# Sheet2.net
KiCad netlist of a schematic drawn in Altium Designer
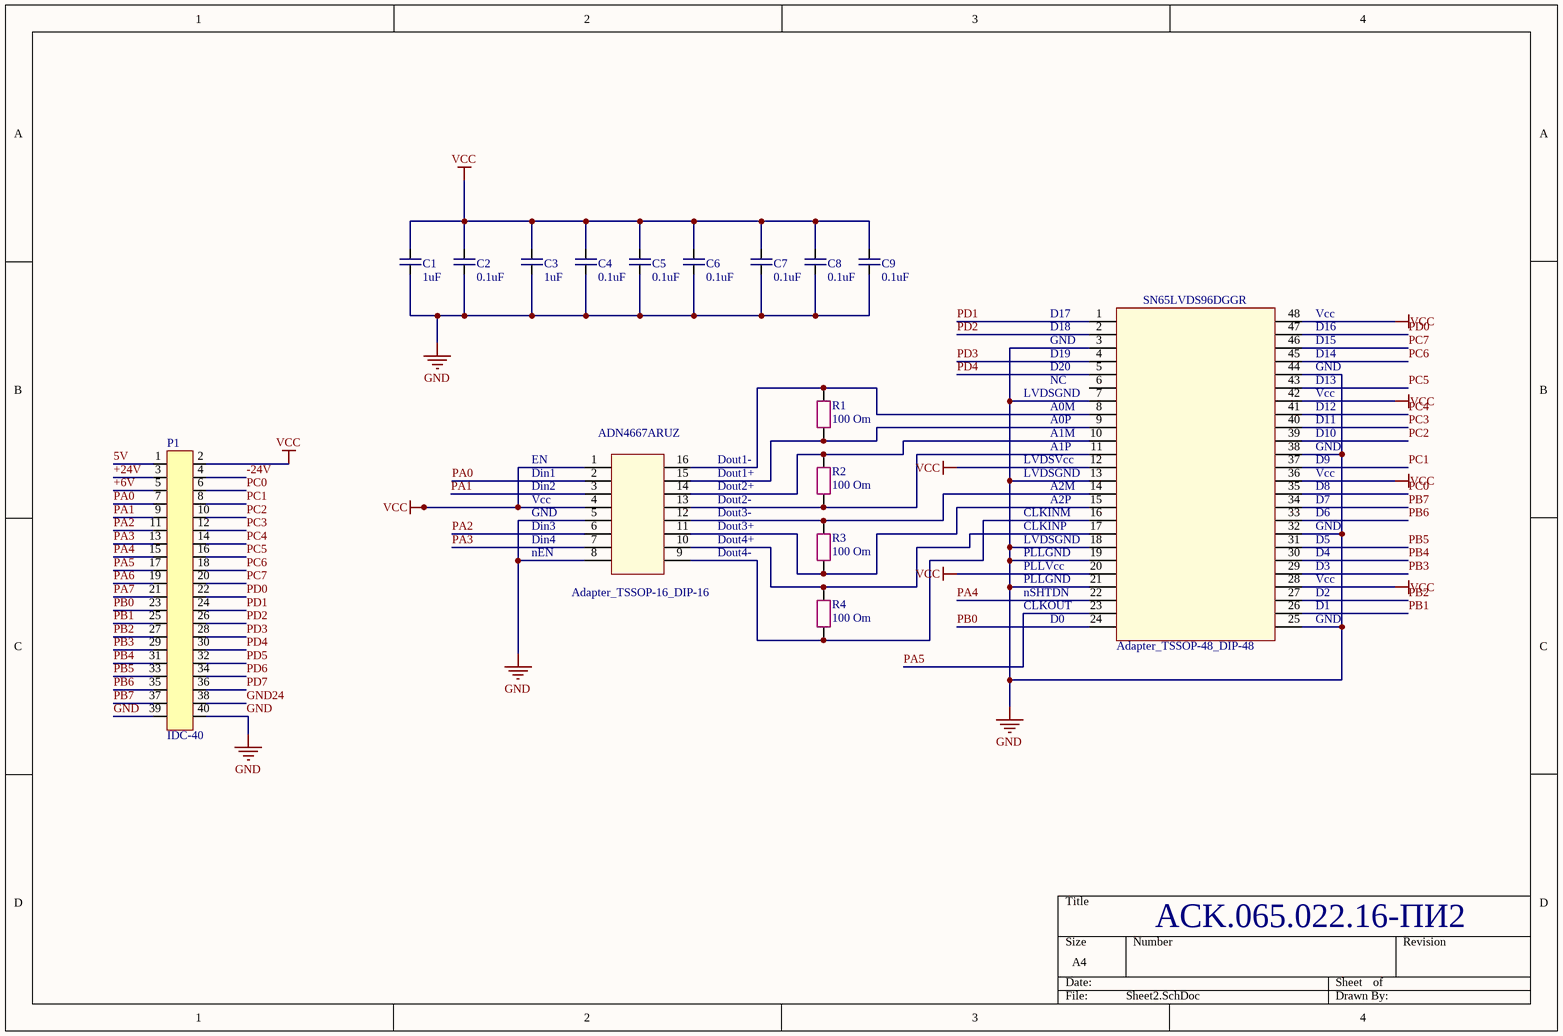
[diagram p0: Sheet2.SchDoc]

(export (version "E")
  (design (tool "Eeschema 10.0.6"))
  (components
    (comp (ref "ADN4667ARUZ")
      (value "Adapter_TSSOP-16_DIP-16")
      (footprint "Adapter_TSSOP-16_DIP-16")
      (libsource (lib "RCU") (part "Adapter_TSSOP-16_DIP-16"))
    )
    (comp (ref "C1") (value "1uF") (footprint "RCU:C_0805") (libsource (lib "RCU") (part "capacitor 0805")))
    (comp (ref "C2") (value "0.1uF") (footprint "RCU:C_0805") (libsource (lib "RCU") (part "capacitor 0805")))
    (comp (ref "C3") (value "1uF") (footprint "RCU:C_0805") (libsource (lib "RCU") (part "capacitor 0805")))
    (comp (ref "C4") (value "0.1uF") (footprint "RCU:C_0805") (libsource (lib "RCU") (part "capacitor 0805")))
    (comp (ref "C5") (value "0.1uF") (footprint "RCU:C_0805") (libsource (lib "RCU") (part "capacitor 0805")))
    (comp (ref "C6") (value "0.1uF") (footprint "RCU:C_0805") (libsource (lib "RCU") (part "capacitor 0805")))
    (comp (ref "C7") (value "0.1uF") (footprint "RCU:C_0805") (libsource (lib "RCU") (part "capacitor 0805")))
    (comp (ref "C8") (value "0.1uF") (footprint "RCU:C_0805") (libsource (lib "RCU") (part "capacitor 0805")))
    (comp (ref "C9") (value "0.1uF") (footprint "RCU:C_0805") (libsource (lib "RCU") (part "capacitor 0805")))
    (comp (ref "P1")
      (value "IDC-40")
      (footprint "IDC-40")
      (description "разъем 2529")
      (libsource (lib "RCU") (part "IDC-40"))
    )
    (comp (ref "R1") (value "100 Om") (footprint "RCU:R_0805") (libsource (lib "RCU") (part "resistor 0805")))
    (comp (ref "R2") (value "100 Om") (footprint "RCU:R_0805") (libsource (lib "RCU") (part "resistor 0805")))
    (comp (ref "R3") (value "100 Om") (footprint "RCU:R_0805") (libsource (lib "RCU") (part "resistor 0805")))
    (comp (ref "R4") (value "100 Om") (footprint "RCU:R_0805") (libsource (lib "RCU") (part "resistor 0805")))
    (comp (ref "SN65LVDS96DGGR")
      (value "Adapter_TSSOP-48_DIP-48")
      (footprint "Adapter_TSSOP-48_DIP-48")
      (libsource (lib "RCU") (part "Adapter_TSSOP-48_DIP-48"))
    )
  )
  (nets
    (net (code "1") (name "/+6V") (class "Default")
      (node (ref "P1") (pin "5") (pinfunction "5_5") (pintype "passive"))
    )
    (net (code "2") (name "/+24V") (class "Default")
      (node (ref "P1") (pin "3") (pinfunction "3_3") (pintype "passive"))
    )
    (net (code "3") (name "/-24V") (class "Default")
      (node (ref "P1") (pin "4") (pinfunction "4_4") (pintype "passive"))
    )
    (net (code "4") (name "/5V") (class "Default")
      (node (ref "P1") (pin "1") (pinfunction "0_1") (pintype "passive"))
    )
    (net (code "5") (name "/GND24") (class "Default")
      (node (ref "P1") (pin "38") (pinfunction "38_38") (pintype "passive"))
    )
    (net (code "6") (name "/PA0") (class "Default")
      (node (ref "ADN4667ARUZ") (pin "2") (pinfunction "2_2") (pintype "passive"))
      (node (ref "P1") (pin "7") (pinfunction "7_7") (pintype "passive"))
    )
    (net (code "7") (name "/PA1") (class "Default")
      (node (ref "ADN4667ARUZ") (pin "3") (pinfunction "3_3") (pintype "passive"))
      (node (ref "P1") (pin "9") (pinfunction "9_9") (pintype "passive"))
    )
    (net (code "8") (name "/PA2") (class "Default")
      (node (ref "ADN4667ARUZ") (pin "6") (pinfunction "6_6") (pintype "passive"))
      (node (ref "P1") (pin "11") (pinfunction "11_11") (pintype "passive"))
    )
    (net (code "9") (name "/PA3") (class "Default")
      (node (ref "ADN4667ARUZ") (pin "7") (pinfunction "7_7") (pintype "passive"))
      (node (ref "P1") (pin "13") (pinfunction "13_13") (pintype "passive"))
    )
    (net (code "10") (name "/PA4") (class "Default")
      (node (ref "P1") (pin "15") (pinfunction "15_15") (pintype "passive"))
      (node (ref "SN65LVDS96DGGR") (pin "22") (pinfunction "22_22") (pintype "passive"))
    )
    (net (code "11") (name "/PA5") (class "Default")
      (node (ref "P1") (pin "17") (pinfunction "17_17") (pintype "passive"))
      (node (ref "SN65LVDS96DGGR") (pin "23") (pinfunction "23_23") (pintype "passive"))
    )
    (net (code "12") (name "/PA6") (class "Default")
      (node (ref "P1") (pin "19") (pinfunction "19_19") (pintype "passive"))
    )
    (net (code "13") (name "/PA7") (class "Default")
      (node (ref "P1") (pin "21") (pinfunction "21_21") (pintype "passive"))
    )
    (net (code "14") (name "/PB0") (class "Default")
      (node (ref "P1") (pin "23") (pinfunction "23_23") (pintype "passive"))
      (node (ref "SN65LVDS96DGGR") (pin "24") (pinfunction "24_24") (pintype "passive"))
    )
    (net (code "15") (name "/PB1") (class "Default")
      (node (ref "P1") (pin "25") (pinfunction "25_25") (pintype "passive"))
      (node (ref "SN65LVDS96DGGR") (pin "26") (pinfunction "26_26") (pintype "passive"))
    )
    (net (code "16") (name "/PB2") (class "Default")
      (node (ref "P1") (pin "27") (pinfunction "27_27") (pintype "passive"))
      (node (ref "SN65LVDS96DGGR") (pin "27") (pinfunction "27_27") (pintype "passive"))
    )
    (net (code "17") (name "/PB3") (class "Default")
      (node (ref "P1") (pin "29") (pinfunction "29_29") (pintype "passive"))
      (node (ref "SN65LVDS96DGGR") (pin "29") (pinfunction "29_29") (pintype "passive"))
    )
    (net (code "18") (name "/PB4") (class "Default")
      (node (ref "P1") (pin "31") (pinfunction "31_31") (pintype "passive"))
      (node (ref "SN65LVDS96DGGR") (pin "30") (pinfunction "30_30") (pintype "passive"))
    )
    (net (code "19") (name "/PB5") (class "Default")
      (node (ref "P1") (pin "33") (pinfunction "33_33") (pintype "passive"))
      (node (ref "SN65LVDS96DGGR") (pin "31") (pinfunction "31_31") (pintype "passive"))
    )
    (net (code "20") (name "/PB6") (class "Default")
      (node (ref "P1") (pin "35") (pinfunction "35_35") (pintype "passive"))
      (node (ref "SN65LVDS96DGGR") (pin "33") (pinfunction "33_33") (pintype "passive"))
    )
    (net (code "21") (name "/PB7") (class "Default")
      (node (ref "P1") (pin "37") (pinfunction "37_37") (pintype "passive"))
      (node (ref "SN65LVDS96DGGR") (pin "34") (pinfunction "34_34") (pintype "passive"))
    )
    (net (code "22") (name "/PC0") (class "Default")
      (node (ref "P1") (pin "6") (pinfunction "6_6") (pintype "passive"))
      (node (ref "SN65LVDS96DGGR") (pin "35") (pinfunction "35_35") (pintype "passive"))
    )
    (net (code "23") (name "/PC1") (class "Default")
      (node (ref "P1") (pin "8") (pinfunction "8_8") (pintype "passive"))
      (node (ref "SN65LVDS96DGGR") (pin "37") (pinfunction "37_37") (pintype "passive"))
    )
    (net (code "24") (name "/PC2") (class "Default")
      (node (ref "P1") (pin "10") (pinfunction "10_10") (pintype "passive"))
      (node (ref "SN65LVDS96DGGR") (pin "39") (pinfunction "39_39") (pintype "passive"))
    )
    (net (code "25") (name "/PC3") (class "Default")
      (node (ref "P1") (pin "12") (pinfunction "12_12") (pintype "passive"))
      (node (ref "SN65LVDS96DGGR") (pin "40") (pinfunction "40_40") (pintype "passive"))
    )
    (net (code "26") (name "/PC4") (class "Default")
      (node (ref "P1") (pin "14") (pinfunction "14_14") (pintype "passive"))
      (node (ref "SN65LVDS96DGGR") (pin "41") (pinfunction "41_41") (pintype "passive"))
    )
    (net (code "27") (name "/PC5") (class "Default")
      (node (ref "P1") (pin "16") (pinfunction "16_16") (pintype "passive"))
      (node (ref "SN65LVDS96DGGR") (pin "43") (pinfunction "43_43") (pintype "passive"))
    )
    (net (code "28") (name "/PC6") (class "Default")
      (node (ref "P1") (pin "18") (pinfunction "18_18") (pintype "passive"))
      (node (ref "SN65LVDS96DGGR") (pin "45") (pinfunction "45_45") (pintype "passive"))
    )
    (net (code "29") (name "/PC7") (class "Default")
      (node (ref "P1") (pin "20") (pinfunction "20_20") (pintype "passive"))
      (node (ref "SN65LVDS96DGGR") (pin "46") (pinfunction "46_46") (pintype "passive"))
    )
    (net (code "30") (name "/PD0") (class "Default")
      (node (ref "P1") (pin "22") (pinfunction "22_22") (pintype "passive"))
      (node (ref "SN65LVDS96DGGR") (pin "47") (pinfunction "47_47") (pintype "passive"))
    )
    (net (code "31") (name "/PD1") (class "Default")
      (node (ref "P1") (pin "24") (pinfunction "24_24") (pintype "passive"))
      (node (ref "SN65LVDS96DGGR") (pin "1") (pinfunction "1_1") (pintype "passive"))
    )
    (net (code "32") (name "/PD2") (class "Default")
      (node (ref "P1") (pin "26") (pinfunction "26_26") (pintype "passive"))
      (node (ref "SN65LVDS96DGGR") (pin "2") (pinfunction "2_2") (pintype "passive"))
    )
    (net (code "33") (name "/PD3") (class "Default")
      (node (ref "P1") (pin "28") (pinfunction "28_28") (pintype "passive"))
      (node (ref "SN65LVDS96DGGR") (pin "4") (pinfunction "4_4") (pintype "passive"))
    )
    (net (code "34") (name "/PD4") (class "Default")
      (node (ref "P1") (pin "30") (pinfunction "30_30") (pintype "passive"))
      (node (ref "SN65LVDS96DGGR") (pin "5") (pinfunction "5_5") (pintype "passive"))
    )
    (net (code "35") (name "/PD5") (class "Default")
      (node (ref "P1") (pin "32") (pinfunction "32_32") (pintype "passive"))
    )
    (net (code "36") (name "/PD6") (class "Default")
      (node (ref "P1") (pin "34") (pinfunction "34_34") (pintype "passive"))
    )
    (net (code "37") (name "/PD7") (class "Default")
      (node (ref "P1") (pin "36") (pinfunction "36_36") (pintype "passive"))
    )
    (net (code "38") (name "GND") (class "Default")
      (node (ref "ADN4667ARUZ") (pin "5") (pinfunction "5_5") (pintype "passive"))
      (node (ref "ADN4667ARUZ") (pin "8") (pinfunction "8_8") (pintype "passive"))
      (node (ref "C1") (pin "2") (pinfunction "2_2") (pintype "passive"))
      (node (ref "C2") (pin "2") (pinfunction "2_2") (pintype "passive"))
      (node (ref "C3") (pin "2") (pinfunction "2_2") (pintype "passive"))
      (node (ref "C4") (pin "2") (pinfunction "2_2") (pintype "passive"))
      (node (ref "C5") (pin "2") (pinfunction "2_2") (pintype "passive"))
      (node (ref "C6") (pin "2") (pinfunction "2_2") (pintype "passive"))
      (node (ref "C7") (pin "2") (pinfunction "2_2") (pintype "passive"))
      (node (ref "C8") (pin "2") (pinfunction "2_2") (pintype "passive"))
      (node (ref "C9") (pin "2") (pinfunction "2_2") (pintype "passive"))
      (node (ref "P1") (pin "39") (pinfunction "39_39") (pintype "passive"))
      (node (ref "P1") (pin "40") (pinfunction "40_40") (pintype "passive"))
      (node (ref "SN65LVDS96DGGR") (pin "13") (pinfunction "13_13") (pintype "passive"))
      (node (ref "SN65LVDS96DGGR") (pin "18") (pinfunction "18_18") (pintype "passive"))
      (node (ref "SN65LVDS96DGGR") (pin "19") (pinfunction "19_19") (pintype "passive"))
      (node (ref "SN65LVDS96DGGR") (pin "21") (pinfunction "21_21") (pintype "passive"))
      (node (ref "SN65LVDS96DGGR") (pin "25") (pinfunction "25_25") (pintype "passive"))
      (node (ref "SN65LVDS96DGGR") (pin "3") (pinfunction "3_3") (pintype "passive"))
      (node (ref "SN65LVDS96DGGR") (pin "32") (pinfunction "32_32") (pintype "passive"))
      (node (ref "SN65LVDS96DGGR") (pin "38") (pinfunction "38_38") (pintype "passive"))
      (node (ref "SN65LVDS96DGGR") (pin "44") (pinfunction "44_44") (pintype "passive"))
      (node (ref "SN65LVDS96DGGR") (pin "7") (pinfunction "7_7") (pintype "passive"))
    )
    (net (code "39") (name "Net-(ADN4667ARUZ-Pad9)") (class "Default")
      (node (ref "ADN4667ARUZ") (pin "9") (pinfunction "9_9") (pintype "passive"))
      (node (ref "R4") (pin "1") (pinfunction "1_1") (pintype "passive"))
      (node (ref "SN65LVDS96DGGR") (pin "16") (pinfunction "16_16") (pintype "passive"))
    )
    (net (code "40") (name "Net-(ADN4667ARUZ-Pad10)") (class "Default")
      (node (ref "ADN4667ARUZ") (pin "10") (pinfunction "10_10") (pintype "passive"))
      (node (ref "R4") (pin "2") (pinfunction "2_2") (pintype "passive"))
      (node (ref "SN65LVDS96DGGR") (pin "17") (pinfunction "17_17") (pintype "passive"))
    )
    (net (code "41") (name "Net-(ADN4667ARUZ-Pad11)") (class "Default")
      (node (ref "ADN4667ARUZ") (pin "11") (pinfunction "11_11") (pintype "passive"))
      (node (ref "R3") (pin "1") (pinfunction "1_1") (pintype "passive"))
      (node (ref "SN65LVDS96DGGR") (pin "15") (pinfunction "15_15") (pintype "passive"))
    )
    (net (code "42") (name "Net-(ADN4667ARUZ-Pad12)") (class "Default")
      (node (ref "ADN4667ARUZ") (pin "12") (pinfunction "12_12") (pintype "passive"))
      (node (ref "R3") (pin "2") (pinfunction "2_2") (pintype "passive"))
      (node (ref "SN65LVDS96DGGR") (pin "14") (pinfunction "14_14") (pintype "passive"))
    )
    (net (code "43") (name "Net-(ADN4667ARUZ-Pad13)") (class "Default")
      (node (ref "ADN4667ARUZ") (pin "13") (pinfunction "13_13") (pintype "passive"))
      (node (ref "R2") (pin "1") (pinfunction "1_1") (pintype "passive"))
      (node (ref "SN65LVDS96DGGR") (pin "11") (pinfunction "11_11") (pintype "passive"))
    )
    (net (code "44") (name "Net-(ADN4667ARUZ-Pad14)") (class "Default")
      (node (ref "ADN4667ARUZ") (pin "14") (pinfunction "14_14") (pintype "passive"))
      (node (ref "R2") (pin "2") (pinfunction "2_2") (pintype "passive"))
      (node (ref "SN65LVDS96DGGR") (pin "10") (pinfunction "10_10") (pintype "passive"))
    )
    (net (code "45") (name "Net-(ADN4667ARUZ-Pad15)") (class "Default")
      (node (ref "ADN4667ARUZ") (pin "15") (pinfunction "15_15") (pintype "passive"))
      (node (ref "R1") (pin "1") (pinfunction "1_1") (pintype "passive"))
      (node (ref "SN65LVDS96DGGR") (pin "9") (pinfunction "9_9") (pintype "passive"))
    )
    (net (code "46") (name "Net-(ADN4667ARUZ-Pad16)") (class "Default")
      (node (ref "ADN4667ARUZ") (pin "16") (pinfunction "16_16") (pintype "passive"))
      (node (ref "R1") (pin "2") (pinfunction "2_2") (pintype "passive"))
      (node (ref "SN65LVDS96DGGR") (pin "8") (pinfunction "8_8") (pintype "passive"))
    )
    (net (code "47") (name "VCC") (class "Default")
      (node (ref "ADN4667ARUZ") (pin "1") (pinfunction "1_1") (pintype "passive"))
      (node (ref "ADN4667ARUZ") (pin "4") (pinfunction "4_4") (pintype "passive"))
      (node (ref "C1") (pin "1") (pinfunction "1_1") (pintype "passive"))
      (node (ref "C2") (pin "1") (pinfunction "1_1") (pintype "passive"))
      (node (ref "C3") (pin "1") (pinfunction "1_1") (pintype "passive"))
      (node (ref "C4") (pin "1") (pinfunction "1_1") (pintype "passive"))
      (node (ref "C5") (pin "1") (pinfunction "1_1") (pintype "passive"))
      (node (ref "C6") (pin "1") (pinfunction "1_1") (pintype "passive"))
      (node (ref "C7") (pin "1") (pinfunction "1_1") (pintype "passive"))
      (node (ref "C8") (pin "1") (pinfunction "1_1") (pintype "passive"))
      (node (ref "C9") (pin "1") (pinfunction "1_1") (pintype "passive"))
      (node (ref "P1") (pin "2") (pinfunction "2_2") (pintype "passive"))
      (node (ref "SN65LVDS96DGGR") (pin "12") (pinfunction "12_12") (pintype "passive"))
      (node (ref "SN65LVDS96DGGR") (pin "20") (pinfunction "20_20") (pintype "passive"))
      (node (ref "SN65LVDS96DGGR") (pin "28") (pinfunction "28_28") (pintype "passive"))
      (node (ref "SN65LVDS96DGGR") (pin "36") (pinfunction "36_36") (pintype "passive"))
      (node (ref "SN65LVDS96DGGR") (pin "42") (pinfunction "42_42") (pintype "passive"))
      (node (ref "SN65LVDS96DGGR") (pin "48") (pinfunction "48_48") (pintype "passive"))
    )
    (net (code "48") (name "unconnected-(SN65LVDS96DGGR-Pad6)") (class "Default")
      (node (ref "SN65LVDS96DGGR") (pin "6") (pinfunction "6_6") (pintype "passive"))
    )
  )
)
